# Schema.net
KiCad netlist of a schematic drawn in EAGLE
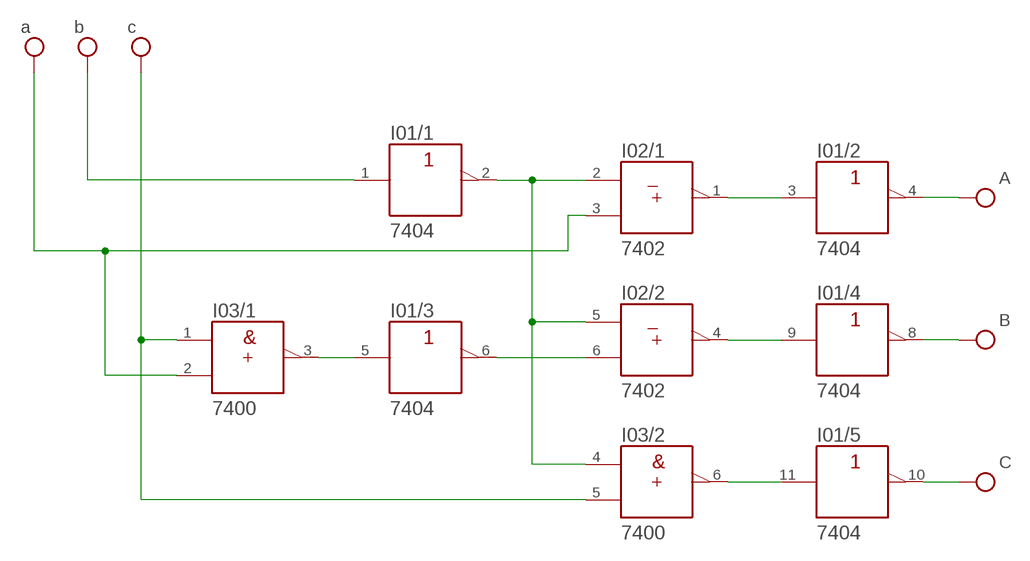
[diagram p0: schematic, sheet 1]

(export (version "E")
  (design (tool "Eeschema 10.0.6"))
  (components
    (comp (ref "I01")
      (value "7404")
      (footprint "eagle-import:DIL14")
      (libsource (lib "eagle-import") (part "7404N"))
    )
    (comp (ref "I02")
      (value "7402")
      (footprint "eagle-import:DIL14")
      (libsource (lib "eagle-import") (part "7402N"))
    )
    (comp (ref "I03")
      (value "7400")
      (footprint "eagle-import:DIL14")
      (libsource (lib "eagle-import") (part "7400N"))
    )
  )
  (nets
    (net (code "1") (name "A") (class "Default")
      (node (ref "I01") (pin "1") (pinfunction "A_1") (pintype "input"))
      (node (ref "I01") (pin "10") (pinfunction "Y_10") (pintype "output"))
      (node (ref "I01") (pin "4") (pinfunction "Y_4") (pintype "output"))
      (node (ref "I01") (pin "8") (pinfunction "Y_8") (pintype "output"))
      (node (ref "I02") (pin "3") (pinfunction "B_3") (pintype "input"))
      (node (ref "I03") (pin "1") (pinfunction "A_1") (pintype "input"))
      (node (ref "I03") (pin "2") (pinfunction "B_2") (pintype "input"))
      (node (ref "I03") (pin "5") (pinfunction "B_5") (pintype "input"))
    )
    (net (code "2") (name "Net-(I01C-Y)") (class "Default")
      (node (ref "I01") (pin "2") (pinfunction "Y_2") (pintype "output"))
      (node (ref "I02") (pin "2") (pinfunction "A_2") (pintype "input"))
      (node (ref "I02") (pin "5") (pinfunction "A_5") (pintype "input"))
      (node (ref "I03") (pin "4") (pinfunction "A_4") (pintype "input"))
    )
    (net (code "3") (name "Net-(I01D-A)") (class "Default")
      (node (ref "I01") (pin "3") (pinfunction "A_3") (pintype "input"))
      (node (ref "I02") (pin "1") (pinfunction "Y_1") (pintype "output"))
    )
    (net (code "4") (name "Net-(I01E-A)") (class "Default")
      (node (ref "I01") (pin "5") (pinfunction "A_5") (pintype "input"))
      (node (ref "I03") (pin "3") (pinfunction "Y_3") (pintype "output"))
    )
    (net (code "5") (name "Net-(I01E-Y)") (class "Default")
      (node (ref "I01") (pin "6") (pinfunction "Y_6") (pintype "output"))
      (node (ref "I02") (pin "6") (pinfunction "B_6") (pintype "input"))
    )
    (net (code "6") (name "Net-(I01F-A)") (class "Default")
      (node (ref "I01") (pin "9") (pinfunction "A_9") (pintype "input"))
      (node (ref "I02") (pin "4") (pinfunction "Y_4") (pintype "output"))
    )
    (net (code "7") (name "Net-(I01G-A)") (class "Default")
      (node (ref "I01") (pin "11") (pinfunction "A_11") (pintype "input"))
      (node (ref "I03") (pin "6") (pinfunction "Y_6") (pintype "output"))
    )
  )
)
